# Four-leg_robot.net
KiCad netlist of a schematic drawn in Altium Designer
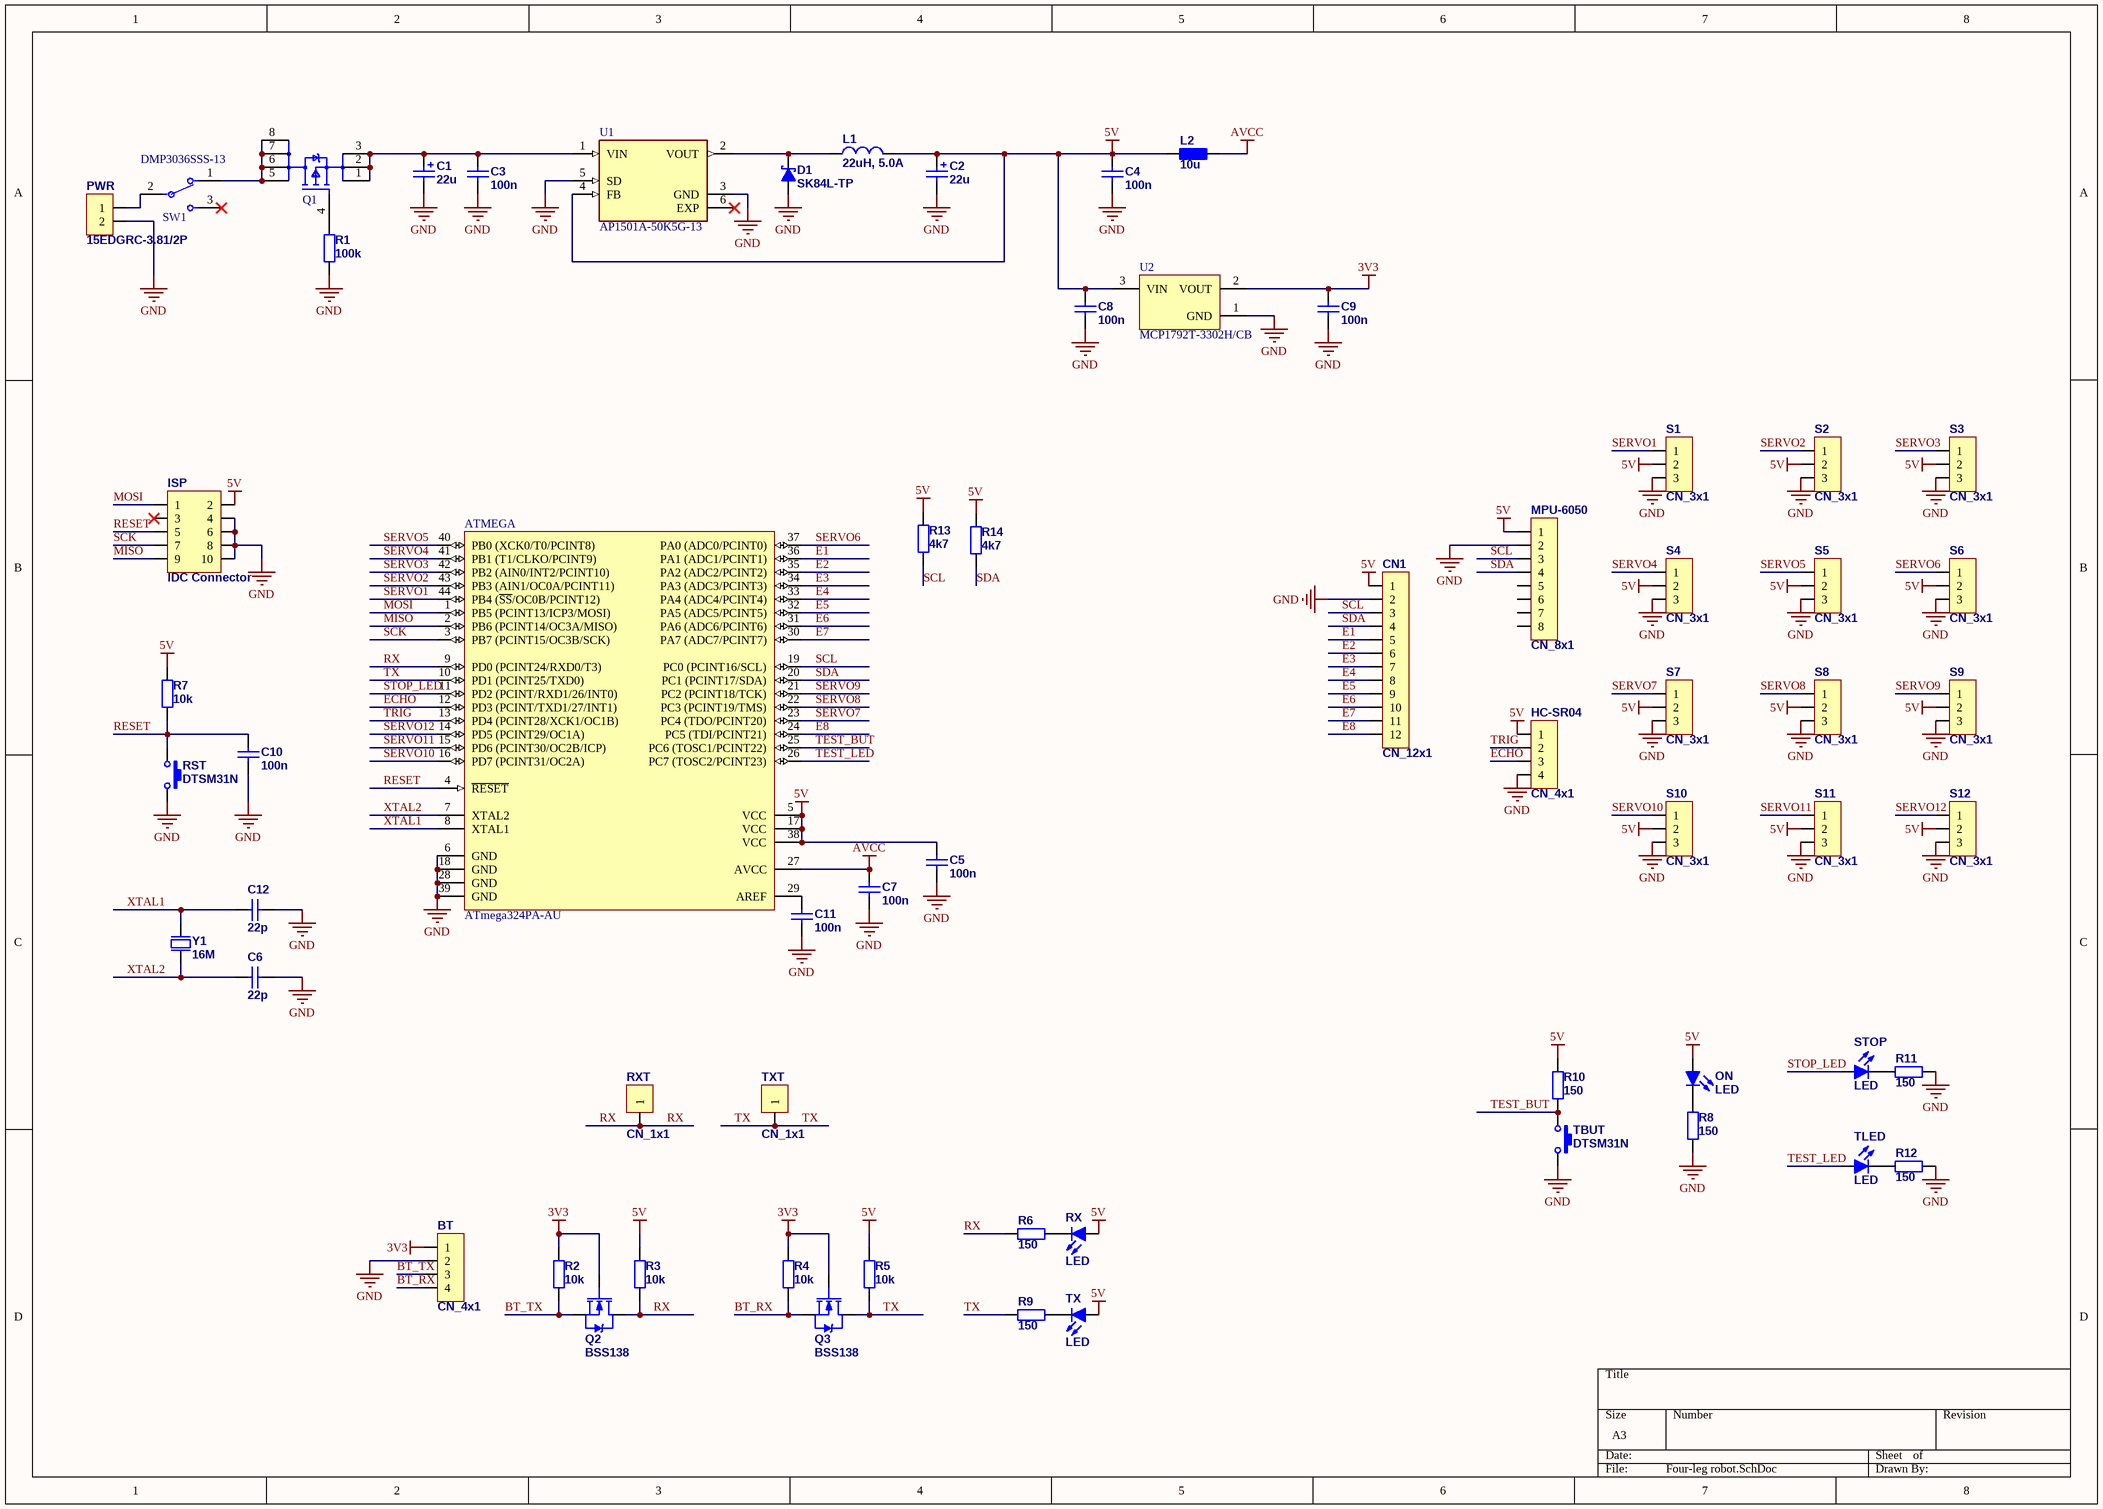
[diagram p0: Four-leg robot.SchDoc]

(export (version "E")
  (design (tool "Eeschema 10.0.6"))
  (components
    (comp (ref "ATMEGA")
      (value "ATmega324PA-AU")
      (footprint "44A_N")
      (libsource (lib "Atmel Microcontroller megaAVR") (part "ATmega324PA-AU"))
    )
    (comp (ref "BT")
      (value "CN_4x1")
      (footprint "GP_4x1_F")
      (libsource (lib "goldpin_female") (part "CN_4x1"))
    )
    (comp (ref "C1")
      (value "22u")
      (footprint "SMDB")
      (description "Polarized Tantalum Capacitor")
      (libsource (lib "capacitors") (part "Cap Pol Tant"))
    )
    (comp (ref "C2")
      (value "22u")
      (footprint "SMDB")
      (description "Polarized Tantalum Capacitor")
      (libsource (lib "capacitors") (part "Cap Pol Tant"))
    )
    (comp (ref "C3")
      (value "100n")
      (footprint "C0805")
      (description "Capacitor")
      (libsource (lib "capacitors") (part "Cap"))
    )
    (comp (ref "C4")
      (value "100n")
      (footprint "C0805")
      (description "Capacitor")
      (libsource (lib "capacitors") (part "Cap"))
    )
    (comp (ref "C5")
      (value "100n")
      (footprint "C0805")
      (description "Capacitor")
      (libsource (lib "capacitors") (part "Cap"))
    )
    (comp (ref "C6")
      (value "22p")
      (footprint "C0805")
      (description "Capacitor")
      (libsource (lib "capacitors") (part "Cap"))
    )
    (comp (ref "C7")
      (value "100n")
      (footprint "C0805")
      (description "Capacitor")
      (libsource (lib "capacitors") (part "Cap"))
    )
    (comp (ref "C8")
      (value "100n")
      (footprint "C0805")
      (description "Capacitor")
      (libsource (lib "capacitors") (part "Cap"))
    )
    (comp (ref "C9")
      (value "100n")
      (footprint "C0805")
      (description "Capacitor")
      (libsource (lib "capacitors") (part "Cap"))
    )
    (comp (ref "C10")
      (value "100n")
      (footprint "C0805")
      (description "Capacitor")
      (libsource (lib "capacitors") (part "Cap"))
    )
    (comp (ref "C11")
      (value "100n")
      (footprint "C0805")
      (description "Capacitor")
      (libsource (lib "capacitors") (part "Cap"))
    )
    (comp (ref "C12")
      (value "22p")
      (footprint "C0805")
      (description "Capacitor")
      (libsource (lib "capacitors") (part "Cap"))
    )
    (comp (ref "CN1")
      (value "CN_12x1")
      (footprint "GP_12x1_F")
      (libsource (lib "goldpin_female") (part "CN_12x1"))
    )
    (comp (ref "D1")
      (value "SK84L-TP")
      (footprint "SMC")
      (description "Schottky Diode: 40V, 5A")
      (libsource (lib "diodes_schottky") (part "SK54C"))
    )
    (comp (ref "HC-SR04")
      (value "CN_4x1")
      (footprint "GP_4x1_F")
      (libsource (lib "goldpin_female") (part "CN_4x1"))
    )
    (comp (ref "ISP") (value "IDC Connector") (footprint "IDC10") (libsource (lib "idc") (part "CN_5x2")))
    (comp (ref "L1")
      (value "22uH, 5.0A")
      (footprint "DE1209")
      (description "DE1209-22")
      (libsource (lib "inductors") (part "DE1209-22"))
    )
    (comp (ref "L2")
      (value "10u")
      (footprint "L0805")
      (description "Inductor")
      (libsource (lib "inductors") (part "Ind2"))
    )
    (comp (ref "MPU-6050")
      (value "CN_8x1")
      (footprint "GP_8x1_F")
      (libsource (lib "goldpin_female") (part "CN_8x1"))
    )
    (comp (ref "ON")
      (value "LED")
      (footprint "LED0805G")
      (description "Typical RED, GREEN, YELLOW, AMBER GaAs LED")
      (libsource (lib "leds") (part "LED"))
    )
    (comp (ref "PWR")
      (value "15EDGRC-3.81/2P")
      (footprint "15EDGRC-3.81/2P_WO_CN")
      (description "Degson 7A, 250V, 2 Pole Plug-in Terminal Block")
      (libsource (lib "terminal_blocks") (part "15EDGRC-3.81/2P"))
    )
    (comp (ref "Q1")
      (value "IRF7425PBF")
      (footprint "Infineon_PG-DSO-8_MFG")
      (libsource (lib "Trans_Infineon_IRF7425PBF_eec") (part "IRF7425PBF"))
    )
    (comp (ref "Q2")
      (value "BSS138")
      (footprint "SOT-23")
      (description "N-Channel Enhancement Mode Vertical DMOS FET")
      (fields (field (name "PUBLISHER") "Altium Limited"))
      (libsource (lib "transistors_mos") (part "BSS138"))
    )
    (comp (ref "Q3")
      (value "BSS138")
      (footprint "SOT-23")
      (description "N-Channel Enhancement Mode Vertical DMOS FET")
      (fields (field (name "PUBLISHER") "Altium Limited"))
      (libsource (lib "transistors_mos") (part "BSS138"))
    )
    (comp (ref "R1")
      (value "100k")
      (footprint "R0805")
      (description "Resistor")
      (libsource (lib "resistors") (part "Res"))
    )
    (comp (ref "R2")
      (value "10k")
      (footprint "R0805")
      (description "Resistor")
      (libsource (lib "resistors") (part "Res"))
    )
    (comp (ref "R3")
      (value "10k")
      (footprint "R0805")
      (description "Resistor")
      (libsource (lib "resistors") (part "Res"))
    )
    (comp (ref "R4")
      (value "10k")
      (footprint "R0805")
      (description "Resistor")
      (libsource (lib "resistors") (part "Res"))
    )
    (comp (ref "R5")
      (value "10k")
      (footprint "R0805")
      (description "Resistor")
      (libsource (lib "resistors") (part "Res"))
    )
    (comp (ref "R6")
      (value "150")
      (footprint "R0805")
      (description "Resistor")
      (libsource (lib "") (part "Res_2"))
    )
    (comp (ref "R7")
      (value "10k")
      (footprint "R0805")
      (description "Resistor")
      (libsource (lib "resistors") (part "Res"))
    )
    (comp (ref "R8")
      (value "150")
      (footprint "R0805")
      (description "Resistor")
      (libsource (lib "resistors") (part "Res"))
    )
    (comp (ref "R9")
      (value "150")
      (footprint "R0805")
      (description "Resistor")
      (libsource (lib "") (part "Res_2"))
    )
    (comp (ref "R10")
      (value "150")
      (footprint "R0805")
      (description "Resistor")
      (libsource (lib "resistors") (part "Res"))
    )
    (comp (ref "R11")
      (value "150")
      (footprint "R0805")
      (description "Resistor")
      (libsource (lib "") (part "Res_2"))
    )
    (comp (ref "R12")
      (value "150")
      (footprint "R0805")
      (description "Resistor")
      (libsource (lib "") (part "Res_2"))
    )
    (comp (ref "R13")
      (value "4k7")
      (footprint "R0805")
      (description "Resistor")
      (libsource (lib "") (part "Res_1"))
    )
    (comp (ref "R14")
      (value "4k7")
      (footprint "R0805")
      (description "Resistor")
      (libsource (lib "") (part "Res_1"))
    )
    (comp (ref "RST")
      (value "DTSM31N")
      (footprint "DTSM-3")
      (description "DIPTRONICS 6x3,5mm SMD Tactile SPST-NO Switch")
      (libsource (lib "microswitches") (part "DTSM31N"))
    )
    (comp (ref "RX")
      (value "LED")
      (footprint "LED0805G")
      (description "Typical RED, GREEN, YELLOW, AMBER GaAs LED")
      (libsource (lib "leds") (part "LED"))
    )
    (comp (ref "RXT") (value "CN_1x1") (footprint "GP_1x1") (libsource (lib "goldpin_male") (part "CN_1x1")))
    (comp (ref "S1") (value "CN_3x1") (footprint "GP_3x1") (libsource (lib "goldpin_male") (part "CN_3x1")))
    (comp (ref "S2") (value "CN_3x1") (footprint "GP_3x1") (libsource (lib "goldpin_male") (part "CN_3x1")))
    (comp (ref "S3") (value "CN_3x1") (footprint "GP_3x1") (libsource (lib "goldpin_male") (part "CN_3x1")))
    (comp (ref "S4") (value "CN_3x1") (footprint "GP_3x1") (libsource (lib "goldpin_male") (part "CN_3x1")))
    (comp (ref "S5") (value "CN_3x1") (footprint "GP_3x1") (libsource (lib "goldpin_male") (part "CN_3x1")))
    (comp (ref "S6") (value "CN_3x1") (footprint "GP_3x1") (libsource (lib "goldpin_male") (part "CN_3x1")))
    (comp (ref "S7") (value "CN_3x1") (footprint "GP_3x1") (libsource (lib "goldpin_male") (part "CN_3x1")))
    (comp (ref "S8") (value "CN_3x1") (footprint "GP_3x1") (libsource (lib "goldpin_male") (part "CN_3x1")))
    (comp (ref "S9") (value "CN_3x1") (footprint "GP_3x1") (libsource (lib "goldpin_male") (part "CN_3x1")))
    (comp (ref "S10") (value "CN_3x1") (footprint "GP_3x1") (libsource (lib "goldpin_male") (part "CN_3x1")))
    (comp (ref "S11") (value "CN_3x1") (footprint "GP_3x1") (libsource (lib "goldpin_male") (part "CN_3x1")))
    (comp (ref "S12") (value "CN_3x1") (footprint "GP_3x1") (libsource (lib "goldpin_male") (part "CN_3x1")))
    (comp (ref "STOP")
      (value "LED")
      (footprint "LED0805G")
      (description "Typical RED, GREEN, YELLOW, AMBER GaAs LED")
      (libsource (lib "leds") (part "LED"))
    )
    (comp (ref "SW1")
      (value "DMP3036SSS-13")
      (footprint "C&K_1101M2S3CQE2_0")
      (description "SWITCH SLIDE SPDT 6A 120V")
      (fields (field (name "PART NUMBER") "1101M2S3CQE2") (field (name "MANUFACTURER") "C&K"))
      (libsource (lib "Switch_C&K_1101M2S3CQE2_eec") (part "Switch_C&K_1101M2S3CQE2_eec"))
    )
    (comp (ref "TBUT")
      (value "DTSM31N")
      (footprint "DTSM-3")
      (description "DIPTRONICS 6x3,5mm SMD Tactile SPST-NO Switch")
      (libsource (lib "microswitches") (part "DTSM31N"))
    )
    (comp (ref "TLED")
      (value "LED")
      (footprint "LED0805G")
      (description "Typical RED, GREEN, YELLOW, AMBER GaAs LED")
      (libsource (lib "leds") (part "LED"))
    )
    (comp (ref "TX")
      (value "LED")
      (footprint "LED0805G")
      (description "Typical RED, GREEN, YELLOW, AMBER GaAs LED")
      (libsource (lib "leds") (part "LED"))
    )
    (comp (ref "TXT") (value "CN_1x1") (footprint "GP_1x1") (libsource (lib "goldpin_male") (part "CN_1x1")))
    (comp (ref "U1")
      (value "AP1501A-50K5G-13")
      (footprint "TO-263-5:TO-263-5")
      (description "Voltage stabiliser; PMIC; 5A; TO263-5; SMD; buck; -20Ã·85Â°C; 800pcs.")
      (libsource (lib "AP1501A-33K5G-13") (part "AP1501A-33K5G-13"))
    )
    (comp (ref "U2")
      (value "MCP1792T-3302H/CB")
      (footprint "SOT-23")
      (fields (field (name "PARTNUMBER") "MCP1703T-3302E/CB"))
      (libsource (lib "Microchip_MCP1703T_3302E_CB") (part "MCP1703T-3302E/CB"))
    )
    (comp (ref "Y1")
      (value "16M")
      (footprint "HC49-S")
      (description "Crystal Oscillator")
      (libsource (lib "quartz_crystals_and_filters") (part "XTAL_2PIN"))
    )
  )
  (nets
    (net (code "1") (name "/BT_RX") (class "Default")
      (node (ref "BT") (pin "4") (pinfunction "4_4") (pintype "passive"))
      (node (ref "Q3") (pin "2") (pinfunction "S_2") (pintype "passive"))
      (node (ref "R4") (pin "1") (pinfunction "1_1") (pintype "passive"))
    )
    (net (code "2") (name "/BT_TX") (class "Default")
      (node (ref "BT") (pin "3") (pinfunction "3_3") (pintype "passive"))
      (node (ref "Q2") (pin "2") (pinfunction "S_2") (pintype "passive"))
      (node (ref "R2") (pin "1") (pinfunction "1_1") (pintype "passive"))
    )
    (net (code "3") (name "/E1") (class "Default")
      (node (ref "ATMEGA") (pin "36") (pinfunction "PA1_(ADC1/PCINT1)_36") (pintype "bidirectional"))
      (node (ref "CN1") (pin "5") (pinfunction "5_5") (pintype "passive"))
    )
    (net (code "4") (name "/E2") (class "Default")
      (node (ref "ATMEGA") (pin "35") (pinfunction "PA2_(ADC2/PCINT2)_35") (pintype "bidirectional"))
      (node (ref "CN1") (pin "6") (pinfunction "6_6") (pintype "passive"))
    )
    (net (code "5") (name "/E3") (class "Default")
      (node (ref "ATMEGA") (pin "34") (pinfunction "PA3_(ADC3/PCINT3)_34") (pintype "bidirectional"))
      (node (ref "CN1") (pin "7") (pinfunction "7_7") (pintype "passive"))
    )
    (net (code "6") (name "/E4") (class "Default")
      (node (ref "ATMEGA") (pin "33") (pinfunction "PA4_(ADC4/PCINT4)_33") (pintype "bidirectional"))
      (node (ref "CN1") (pin "8") (pinfunction "8_8") (pintype "passive"))
    )
    (net (code "7") (name "/E5") (class "Default")
      (node (ref "ATMEGA") (pin "32") (pinfunction "PA5_(ADC5/PCINT5)_32") (pintype "bidirectional"))
      (node (ref "CN1") (pin "9") (pinfunction "9_9") (pintype "passive"))
    )
    (net (code "8") (name "/E6") (class "Default")
      (node (ref "ATMEGA") (pin "31") (pinfunction "PA6_(ADC6/PCINT6)_31") (pintype "bidirectional"))
      (node (ref "CN1") (pin "10") (pinfunction "10_10") (pintype "passive"))
    )
    (net (code "9") (name "/E7") (class "Default")
      (node (ref "ATMEGA") (pin "30") (pinfunction "PA7_(ADC7/PCINT7)_30") (pintype "bidirectional"))
      (node (ref "CN1") (pin "11") (pinfunction "11_11") (pintype "passive"))
    )
    (net (code "10") (name "/E8") (class "Default")
      (node (ref "ATMEGA") (pin "24") (pinfunction "PC5_(TDI/PCINT21)_24") (pintype "bidirectional"))
      (node (ref "CN1") (pin "12") (pinfunction "12_12") (pintype "passive"))
    )
    (net (code "11") (name "/ECHO") (class "Default")
      (node (ref "ATMEGA") (pin "12") (pinfunction "PD3_(PCINT/TXD1/27/INT1)_12") (pintype "bidirectional"))
      (node (ref "HC-SR04") (pin "3") (pinfunction "3_3") (pintype "passive"))
    )
    (net (code "12") (name "/MISO") (class "Default")
      (node (ref "ATMEGA") (pin "2") (pinfunction "PB6_(PCINT14/OC3A/MISO)_2") (pintype "bidirectional"))
      (node (ref "ISP") (pin "9") (pinfunction "9_9") (pintype "passive"))
    )
    (net (code "13") (name "/MOSI") (class "Default")
      (node (ref "ATMEGA") (pin "1") (pinfunction "PB5_(PCINT13/ICP3/MOSI)_1") (pintype "bidirectional"))
      (node (ref "ISP") (pin "1") (pinfunction "1_1") (pintype "passive"))
    )
    (net (code "14") (name "/RESET") (class "Default")
      (node (ref "ATMEGA") (pin "4") (pinfunction "~{RESET}_4") (pintype "input"))
      (node (ref "C10") (pin "2") (pinfunction "2_2") (pintype "passive"))
      (node (ref "ISP") (pin "5") (pinfunction "5_5") (pintype "passive"))
      (node (ref "R7") (pin "1") (pinfunction "1_1") (pintype "passive"))
      (node (ref "RST") (pin "1") (pinfunction "1_1") (pintype "passive"))
    )
    (net (code "15") (name "/RX") (class "Default")
      (node (ref "ATMEGA") (pin "9") (pinfunction "PD0_(PCINT24/RXD0/T3)_9") (pintype "bidirectional"))
      (node (ref "Q2") (pin "3") (pinfunction "D_3") (pintype "passive"))
      (node (ref "R3") (pin "1") (pinfunction "1_1") (pintype "passive"))
      (node (ref "R6") (pin "1") (pinfunction "1_1") (pintype "passive"))
      (node (ref "RXT") (pin "1") (pinfunction "1_1") (pintype "passive"))
    )
    (net (code "16") (name "/SCK") (class "Default")
      (node (ref "ATMEGA") (pin "3") (pinfunction "PB7_(PCINT15/OC3B/SCK)_3") (pintype "bidirectional"))
      (node (ref "ISP") (pin "7") (pinfunction "7_7") (pintype "passive"))
    )
    (net (code "17") (name "/SCL") (class "Default")
      (node (ref "ATMEGA") (pin "19") (pinfunction "PC0_(PCINT16/SCL)_19") (pintype "bidirectional"))
      (node (ref "CN1") (pin "3") (pinfunction "3_3") (pintype "passive"))
      (node (ref "MPU-6050") (pin "3") (pinfunction "3_3") (pintype "passive"))
      (node (ref "R13") (pin "2") (pinfunction "2_2") (pintype "passive"))
    )
    (net (code "18") (name "/SDA") (class "Default")
      (node (ref "ATMEGA") (pin "20") (pinfunction "PC1_(PCINT17/SDA)_20") (pintype "bidirectional"))
      (node (ref "CN1") (pin "4") (pinfunction "4_4") (pintype "passive"))
      (node (ref "MPU-6050") (pin "4") (pinfunction "4_4") (pintype "passive"))
      (node (ref "R14") (pin "2") (pinfunction "2_2") (pintype "passive"))
    )
    (net (code "19") (name "/SERVO1") (class "Default")
      (node (ref "ATMEGA") (pin "44") (pinfunction "PB4_(~{SS}/OC0B/PCINT12)_44") (pintype "bidirectional"))
      (node (ref "S1") (pin "1") (pinfunction "1_1") (pintype "passive"))
    )
    (net (code "20") (name "/SERVO2") (class "Default")
      (node (ref "ATMEGA") (pin "43") (pinfunction "PB3_(AIN1/OC0A/PCINT11)_43") (pintype "bidirectional"))
      (node (ref "S2") (pin "1") (pinfunction "1_1") (pintype "passive"))
    )
    (net (code "21") (name "/SERVO3") (class "Default")
      (node (ref "ATMEGA") (pin "42") (pinfunction "PB2_(AIN0/INT2/PCINT10)_42") (pintype "bidirectional"))
      (node (ref "S3") (pin "1") (pinfunction "1_1") (pintype "passive"))
    )
    (net (code "22") (name "/SERVO4") (class "Default")
      (node (ref "ATMEGA") (pin "41") (pinfunction "PB1_(T1/CLKO/PCINT9)_41") (pintype "bidirectional"))
      (node (ref "S4") (pin "1") (pinfunction "1_1") (pintype "passive"))
    )
    (net (code "23") (name "/SERVO5") (class "Default")
      (node (ref "ATMEGA") (pin "40") (pinfunction "PB0_(XCK0/T0/PCINT8)_40") (pintype "bidirectional"))
      (node (ref "S5") (pin "1") (pinfunction "1_1") (pintype "passive"))
    )
    (net (code "24") (name "/SERVO6") (class "Default")
      (node (ref "ATMEGA") (pin "37") (pinfunction "PA0_(ADC0/PCINT0)_37") (pintype "bidirectional"))
      (node (ref "S6") (pin "1") (pinfunction "1_1") (pintype "passive"))
    )
    (net (code "25") (name "/SERVO7") (class "Default")
      (node (ref "ATMEGA") (pin "23") (pinfunction "PC4_(TDO/PCINT20)_23") (pintype "bidirectional"))
      (node (ref "S7") (pin "1") (pinfunction "1_1") (pintype "passive"))
    )
    (net (code "26") (name "/SERVO8") (class "Default")
      (node (ref "ATMEGA") (pin "22") (pinfunction "PC3_(PCINT19/TMS)_22") (pintype "bidirectional"))
      (node (ref "S8") (pin "1") (pinfunction "1_1") (pintype "passive"))
    )
    (net (code "27") (name "/SERVO9") (class "Default")
      (node (ref "ATMEGA") (pin "21") (pinfunction "PC2_(PCINT18/TCK)_21") (pintype "bidirectional"))
      (node (ref "S9") (pin "1") (pinfunction "1_1") (pintype "passive"))
    )
    (net (code "28") (name "/SERVO10") (class "Default")
      (node (ref "ATMEGA") (pin "16") (pinfunction "PD7_(PCINT31/OC2A)_16") (pintype "bidirectional"))
      (node (ref "S10") (pin "1") (pinfunction "1_1") (pintype "passive"))
    )
    (net (code "29") (name "/SERVO11") (class "Default")
      (node (ref "ATMEGA") (pin "15") (pinfunction "PD6_(PCINT30/OC2B/ICP)_15") (pintype "bidirectional"))
      (node (ref "S11") (pin "1") (pinfunction "1_1") (pintype "passive"))
    )
    (net (code "30") (name "/SERVO12") (class "Default")
      (node (ref "ATMEGA") (pin "14") (pinfunction "PD5_(PCINT29/OC1A)_14") (pintype "bidirectional"))
      (node (ref "S12") (pin "1") (pinfunction "1_1") (pintype "passive"))
    )
    (net (code "31") (name "/STOP_LED") (class "Default")
      (node (ref "ATMEGA") (pin "11") (pinfunction "PD2_(PCINT/RXD1/26/INT0)_11") (pintype "bidirectional"))
      (node (ref "STOP") (pin "1") (pinfunction "A_1") (pintype "passive"))
    )
    (net (code "32") (name "/TEST_BUT") (class "Default")
      (node (ref "ATMEGA") (pin "25") (pinfunction "PC6_(TOSC1/PCINT22)_25") (pintype "bidirectional"))
      (node (ref "R10") (pin "1") (pinfunction "1_1") (pintype "passive"))
      (node (ref "TBUT") (pin "1") (pinfunction "1_1") (pintype "passive"))
    )
    (net (code "33") (name "/TEST_LED") (class "Default")
      (node (ref "ATMEGA") (pin "26") (pinfunction "PC7_(TOSC2/PCINT23)_26") (pintype "bidirectional"))
      (node (ref "TLED") (pin "1") (pinfunction "A_1") (pintype "passive"))
    )
    (net (code "34") (name "/TRIG") (class "Default")
      (node (ref "ATMEGA") (pin "13") (pinfunction "PD4_(PCINT28/XCK1/OC1B)_13") (pintype "bidirectional"))
      (node (ref "HC-SR04") (pin "2") (pinfunction "2_2") (pintype "passive"))
    )
    (net (code "35") (name "/TX") (class "Default")
      (node (ref "ATMEGA") (pin "10") (pinfunction "PD1_(PCINT25/TXD0)_10") (pintype "bidirectional"))
      (node (ref "Q3") (pin "3") (pinfunction "D_3") (pintype "passive"))
      (node (ref "R5") (pin "1") (pinfunction "1_1") (pintype "passive"))
      (node (ref "R9") (pin "1") (pinfunction "1_1") (pintype "passive"))
      (node (ref "TXT") (pin "1") (pinfunction "1_1") (pintype "passive"))
    )
    (net (code "36") (name "/XTAL1") (class "Default")
      (node (ref "ATMEGA") (pin "8") (pinfunction "XTAL1_8") (pintype "passive"))
      (node (ref "C12") (pin "2") (pinfunction "2_2") (pintype "passive"))
      (node (ref "Y1") (pin "2") (pinfunction "OSC2_2") (pintype "passive"))
    )
    (net (code "37") (name "/XTAL2") (class "Default")
      (node (ref "ATMEGA") (pin "7") (pinfunction "XTAL2_7") (pintype "passive"))
      (node (ref "C6") (pin "2") (pinfunction "2_2") (pintype "passive"))
      (node (ref "Y1") (pin "1") (pinfunction "OSC1_1") (pintype "passive"))
    )
    (net (code "38") (name "3V3") (class "Default")
      (node (ref "BT") (pin "1") (pinfunction "1_1") (pintype "passive"))
      (node (ref "C9") (pin "2") (pinfunction "2_2") (pintype "passive"))
      (node (ref "Q2") (pin "1") (pinfunction "G_1") (pintype "passive"))
      (node (ref "Q3") (pin "1") (pinfunction "G_1") (pintype "passive"))
      (node (ref "R2") (pin "2") (pinfunction "2_2") (pintype "passive"))
      (node (ref "R4") (pin "2") (pinfunction "2_2") (pintype "passive"))
      (node (ref "U2") (pin "2") (pinfunction "VOUT_2") (pintype "power_in"))
    )
    (net (code "39") (name "5V") (class "Default")
      (node (ref "ATMEGA") (pin "17") (pinfunction "VCC_17") (pintype "power_in"))
      (node (ref "ATMEGA") (pin "38") (pinfunction "VCC_38") (pintype "power_in"))
      (node (ref "ATMEGA") (pin "5") (pinfunction "VCC_5") (pintype "power_in"))
      (node (ref "C2") (pin "1") (pinfunction "1_1") (pintype "passive"))
      (node (ref "C4") (pin "2") (pinfunction "2_2") (pintype "passive"))
      (node (ref "C5") (pin "2") (pinfunction "2_2") (pintype "passive"))
      (node (ref "C8") (pin "2") (pinfunction "2_2") (pintype "passive"))
      (node (ref "CN1") (pin "1") (pinfunction "1_1") (pintype "passive"))
      (node (ref "HC-SR04") (pin "1") (pinfunction "1_1") (pintype "passive"))
      (node (ref "ISP") (pin "2") (pinfunction "2_2") (pintype "passive"))
      (node (ref "L1") (pin "2") (pinfunction "2_2") (pintype "passive"))
      (node (ref "L2") (pin "1") (pinfunction "1_1") (pintype "passive"))
      (node (ref "MPU-6050") (pin "1") (pinfunction "1_1") (pintype "passive"))
      (node (ref "ON") (pin "1") (pinfunction "A_1") (pintype "passive"))
      (node (ref "R10") (pin "2") (pinfunction "2_2") (pintype "passive"))
      (node (ref "R13") (pin "1") (pinfunction "1_1") (pintype "passive"))
      (node (ref "R14") (pin "1") (pinfunction "1_1") (pintype "passive"))
      (node (ref "R3") (pin "2") (pinfunction "2_2") (pintype "passive"))
      (node (ref "R5") (pin "2") (pinfunction "2_2") (pintype "passive"))
      (node (ref "R7") (pin "2") (pinfunction "2_2") (pintype "passive"))
      (node (ref "RX") (pin "1") (pinfunction "A_1") (pintype "passive"))
      (node (ref "S1") (pin "2") (pinfunction "2_2") (pintype "passive"))
      (node (ref "S10") (pin "2") (pinfunction "2_2") (pintype "passive"))
      (node (ref "S11") (pin "2") (pinfunction "2_2") (pintype "passive"))
      (node (ref "S12") (pin "2") (pinfunction "2_2") (pintype "passive"))
      (node (ref "S2") (pin "2") (pinfunction "2_2") (pintype "passive"))
      (node (ref "S3") (pin "2") (pinfunction "2_2") (pintype "passive"))
      (node (ref "S4") (pin "2") (pinfunction "2_2") (pintype "passive"))
      (node (ref "S5") (pin "2") (pinfunction "2_2") (pintype "passive"))
      (node (ref "S6") (pin "2") (pinfunction "2_2") (pintype "passive"))
      (node (ref "S7") (pin "2") (pinfunction "2_2") (pintype "passive"))
      (node (ref "S8") (pin "2") (pinfunction "2_2") (pintype "passive"))
      (node (ref "S9") (pin "2") (pinfunction "2_2") (pintype "passive"))
      (node (ref "TX") (pin "1") (pinfunction "A_1") (pintype "passive"))
      (node (ref "U1") (pin "4") (pinfunction "FB_4") (pintype "input"))
      (node (ref "U2") (pin "3") (pinfunction "VIN_3") (pintype "power_in"))
    )
    (net (code "40") (name "AVCC") (class "Default")
      (node (ref "ATMEGA") (pin "27") (pinfunction "AVCC_27") (pintype "power_in"))
      (node (ref "C7") (pin "2") (pinfunction "2_2") (pintype "passive"))
      (node (ref "L2") (pin "2") (pinfunction "2_2") (pintype "passive"))
    )
    (net (code "41") (name "GND") (class "Default")
      (node (ref "ATMEGA") (pin "18") (pinfunction "GND_18") (pintype "power_in"))
      (node (ref "ATMEGA") (pin "28") (pinfunction "GND_28") (pintype "power_in"))
      (node (ref "ATMEGA") (pin "39") (pinfunction "GND_39") (pintype "power_in"))
      (node (ref "ATMEGA") (pin "6") (pinfunction "GND_6") (pintype "power_in"))
      (node (ref "BT") (pin "2") (pinfunction "2_2") (pintype "passive"))
      (node (ref "C1") (pin "2") (pinfunction "2_2") (pintype "passive"))
      (node (ref "C10") (pin "1") (pinfunction "1_1") (pintype "passive"))
      (node (ref "C11") (pin "1") (pinfunction "1_1") (pintype "passive"))
      (node (ref "C12") (pin "1") (pinfunction "1_1") (pintype "passive"))
      (node (ref "C2") (pin "2") (pinfunction "2_2") (pintype "passive"))
      (node (ref "C3") (pin "1") (pinfunction "1_1") (pintype "passive"))
      (node (ref "C4") (pin "1") (pinfunction "1_1") (pintype "passive"))
      (node (ref "C5") (pin "1") (pinfunction "1_1") (pintype "passive"))
      (node (ref "C6") (pin "1") (pinfunction "1_1") (pintype "passive"))
      (node (ref "C7") (pin "1") (pinfunction "1_1") (pintype "passive"))
      (node (ref "C8") (pin "1") (pinfunction "1_1") (pintype "passive"))
      (node (ref "C9") (pin "1") (pinfunction "1_1") (pintype "passive"))
      (node (ref "CN1") (pin "2") (pinfunction "2_2") (pintype "passive"))
      (node (ref "D1") (pin "1") (pinfunction "A_1") (pintype "passive"))
      (node (ref "HC-SR04") (pin "4") (pinfunction "4_4") (pintype "passive"))
      (node (ref "ISP") (pin "10") (pinfunction "10_10") (pintype "passive"))
      (node (ref "ISP") (pin "4") (pinfunction "4_4") (pintype "passive"))
      (node (ref "ISP") (pin "6") (pinfunction "6_6") (pintype "passive"))
      (node (ref "ISP") (pin "8") (pinfunction "8_8") (pintype "passive"))
      (node (ref "MPU-6050") (pin "2") (pinfunction "2_2") (pintype "passive"))
      (node (ref "PWR") (pin "2") (pinfunction "2_2") (pintype "passive"))
      (node (ref "R1") (pin "1") (pinfunction "1_1") (pintype "passive"))
      (node (ref "R11") (pin "2") (pinfunction "2_2") (pintype "passive"))
      (node (ref "R12") (pin "2") (pinfunction "2_2") (pintype "passive"))
      (node (ref "R8") (pin "1") (pinfunction "1_1") (pintype "passive"))
      (node (ref "RST") (pin "2") (pinfunction "2_2") (pintype "passive"))
      (node (ref "S1") (pin "3") (pinfunction "3_3") (pintype "passive"))
      (node (ref "S10") (pin "3") (pinfunction "3_3") (pintype "passive"))
      (node (ref "S11") (pin "3") (pinfunction "3_3") (pintype "passive"))
      (node (ref "S12") (pin "3") (pinfunction "3_3") (pintype "passive"))
      (node (ref "S2") (pin "3") (pinfunction "3_3") (pintype "passive"))
      (node (ref "S3") (pin "3") (pinfunction "3_3") (pintype "passive"))
      (node (ref "S4") (pin "3") (pinfunction "3_3") (pintype "passive"))
      (node (ref "S5") (pin "3") (pinfunction "3_3") (pintype "passive"))
      (node (ref "S6") (pin "3") (pinfunction "3_3") (pintype "passive"))
      (node (ref "S7") (pin "3") (pinfunction "3_3") (pintype "passive"))
      (node (ref "S8") (pin "3") (pinfunction "3_3") (pintype "passive"))
      (node (ref "S9") (pin "3") (pinfunction "3_3") (pintype "passive"))
      (node (ref "TBUT") (pin "2") (pinfunction "2_2") (pintype "passive"))
      (node (ref "U1") (pin "3") (pinfunction "GND_3") (pintype "power_in"))
      (node (ref "U1") (pin "5") (pinfunction "SD_5") (pintype "input"))
      (node (ref "U2") (pin "1") (pinfunction "GND_1") (pintype "power_in"))
    )
    (net (code "42") (name "Net-(ATMEGA-AREF)") (class "Default")
      (node (ref "ATMEGA") (pin "29") (pinfunction "AREF_29") (pintype "power_in"))
      (node (ref "C11") (pin "2") (pinfunction "2_2") (pintype "passive"))
    )
    (net (code "43") (name "Net-(D1-K)") (class "Default")
      (node (ref "D1") (pin "2") (pinfunction "K_2") (pintype "passive"))
      (node (ref "L1") (pin "1") (pinfunction "1_1") (pintype "passive"))
      (node (ref "U1") (pin "2") (pinfunction "VOUT_2") (pintype "output"))
    )
    (net (code "44") (name "Net-(ON-K)") (class "Default")
      (node (ref "ON") (pin "2") (pinfunction "K_2") (pintype "passive"))
      (node (ref "R8") (pin "2") (pinfunction "2_2") (pintype "passive"))
    )
    (net (code "45") (name "Net-(Q1-D-Pad5)") (class "Default")
      (node (ref "Q1") (pin "5") (pinfunction "D_5") (pintype "passive"))
      (node (ref "Q1") (pin "6") (pinfunction "D_6") (pintype "passive"))
      (node (ref "Q1") (pin "7") (pinfunction "D_7") (pintype "passive"))
      (node (ref "Q1") (pin "8") (pinfunction "D_8") (pintype "passive"))
      (node (ref "SW1") (pin "1") (pinfunction "1_1") (pintype "passive"))
    )
    (net (code "46") (name "Net-(Q1-G)") (class "Default")
      (node (ref "Q1") (pin "4") (pinfunction "G_4") (pintype "passive"))
      (node (ref "R1") (pin "2") (pinfunction "2_2") (pintype "passive"))
    )
    (net (code "47") (name "Net-(RX-K)") (class "Default")
      (node (ref "R6") (pin "2") (pinfunction "2_2") (pintype "passive"))
      (node (ref "RX") (pin "2") (pinfunction "K_2") (pintype "passive"))
    )
    (net (code "48") (name "Net-(STOP-K)") (class "Default")
      (node (ref "R11") (pin "1") (pinfunction "1_1") (pintype "passive"))
      (node (ref "STOP") (pin "2") (pinfunction "K_2") (pintype "passive"))
    )
    (net (code "49") (name "Net-(SW1-COM)") (class "Default")
      (node (ref "PWR") (pin "1") (pinfunction "1_1") (pintype "passive"))
      (node (ref "SW1") (pin "2") (pinfunction "COM_2") (pintype "passive"))
    )
    (net (code "50") (name "Net-(TLED-K)") (class "Default")
      (node (ref "R12") (pin "1") (pinfunction "1_1") (pintype "passive"))
      (node (ref "TLED") (pin "2") (pinfunction "K_2") (pintype "passive"))
    )
    (net (code "51") (name "Net-(TX-K)") (class "Default")
      (node (ref "R9") (pin "2") (pinfunction "2_2") (pintype "passive"))
      (node (ref "TX") (pin "2") (pinfunction "K_2") (pintype "passive"))
    )
    (net (code "52") (name "Net-(U1-VIN)") (class "Default")
      (node (ref "C1") (pin "1") (pinfunction "1_1") (pintype "passive"))
      (node (ref "C3") (pin "2") (pinfunction "2_2") (pintype "passive"))
      (node (ref "Q1") (pin "1") (pinfunction "S_1") (pintype "passive"))
      (node (ref "Q1") (pin "2") (pinfunction "S_2") (pintype "passive"))
      (node (ref "Q1") (pin "3") (pinfunction "S_3") (pintype "passive"))
      (node (ref "U1") (pin "1") (pinfunction "VIN_1") (pintype "input"))
    )
    (net (code "53") (name "unconnected-(ISP-Pad3)") (class "Default")
      (node (ref "ISP") (pin "3") (pinfunction "3_3") (pintype "passive+no_connect"))
    )
    (net (code "54") (name "unconnected-(MPU-6050-Pad5)") (class "Default")
      (node (ref "MPU-6050") (pin "5") (pinfunction "5_5") (pintype "passive"))
    )
    (net (code "55") (name "unconnected-(MPU-6050-Pad6)") (class "Default")
      (node (ref "MPU-6050") (pin "6") (pinfunction "6_6") (pintype "passive"))
    )
    (net (code "56") (name "unconnected-(MPU-6050-Pad7)") (class "Default")
      (node (ref "MPU-6050") (pin "7") (pinfunction "7_7") (pintype "passive"))
    )
    (net (code "57") (name "unconnected-(MPU-6050-Pad8)") (class "Default")
      (node (ref "MPU-6050") (pin "8") (pinfunction "8_8") (pintype "passive"))
    )
    (net (code "58") (name "unconnected-(SW1-Pad3)") (class "Default")
      (node (ref "SW1") (pin "3") (pinfunction "3_3") (pintype "passive+no_connect"))
    )
    (net (code "59") (name "unconnected-(U1-EXP-Pad6)") (class "Default")
      (node (ref "U1") (pin "6") (pinfunction "EXP_6") (pintype "power_in+no_connect"))
    )
  )
)
